# pcb.net
KiCad netlist of a schematic drawn in EAGLE
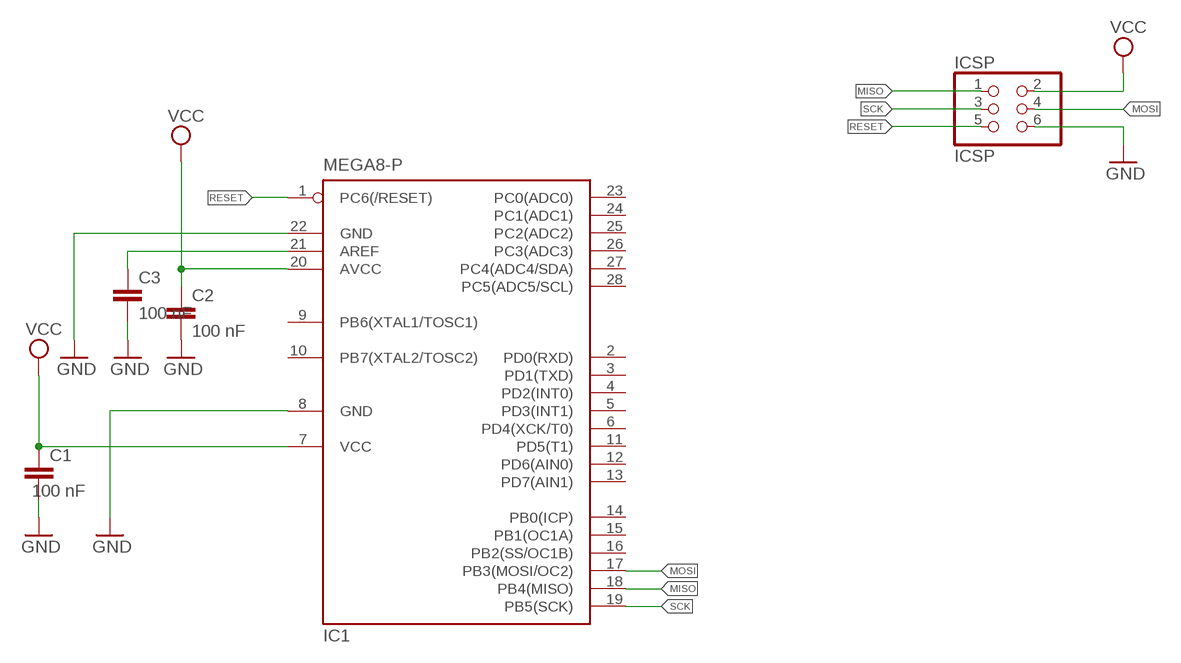
[diagram p0: schematic, sheet 1]

(export (version "E")
  (design (tool "Eeschema 10.0.6"))
  (components
    (comp (ref "C1")
      (value "100 nF")
      (footprint "eagle-import:C025-024X044")
      (libsource (lib "eagle-import") (part "C-EU025-024X044"))
    )
    (comp (ref "C2")
      (value "100 nF")
      (footprint "eagle-import:C025-024X044")
      (libsource (lib "eagle-import") (part "C-EU025-024X044"))
    )
    (comp (ref "C3")
      (value "100 nF")
      (footprint "eagle-import:C025-024X044")
      (libsource (lib "eagle-import") (part "C-EU025-024X044"))
    )
    (comp (ref "IC1")
      (value "MEGA8-P")
      (footprint "eagle-import:DIL28-3")
      (libsource (lib "eagle-import") (part "MEGA8-P"))
    )
    (comp (ref "ICSP")
      (value "ICSP")
      (footprint "eagle-import:2X03")
      (libsource (lib "eagle-import") (part "PINHD-2X3"))
    )
  )
  (nets
    (net (code "1") (name "GND") (class "Default")
      (node (ref "C1") (pin "2") (pinfunction "2_2") (pintype "passive"))
      (node (ref "C2") (pin "2") (pinfunction "2_2") (pintype "passive"))
      (node (ref "C3") (pin "2") (pinfunction "2_2") (pintype "passive"))
      (node (ref "IC1") (pin "22") (pinfunction "GND_22") (pintype "power_in"))
      (node (ref "IC1") (pin "8") (pinfunction "GND_8") (pintype "power_in"))
      (node (ref "ICSP") (pin "6") (pinfunction "6_6") (pintype "passive"))
    )
    (net (code "2") (name "MISO") (class "Default")
      (node (ref "IC1") (pin "18") (pinfunction "PB4(MISO)_18") (pintype "bidirectional"))
      (node (ref "ICSP") (pin "1") (pinfunction "1_1") (pintype "passive"))
    )
    (net (code "3") (name "MOSI") (class "Default")
      (node (ref "IC1") (pin "17") (pinfunction "PB3(MOSI/OC2)_17") (pintype "bidirectional"))
      (node (ref "ICSP") (pin "4") (pinfunction "4_4") (pintype "passive"))
    )
    (net (code "4") (name "Net-(IC1-AREF)") (class "Default")
      (node (ref "C3") (pin "1") (pinfunction "1_1") (pintype "passive"))
      (node (ref "IC1") (pin "21") (pinfunction "AREF_21") (pintype "passive"))
    )
    (net (code "5") (name "RESET") (class "Default")
      (node (ref "IC1") (pin "1") (pinfunction "PC6(/RESET)_1") (pintype "bidirectional"))
      (node (ref "ICSP") (pin "5") (pinfunction "5_5") (pintype "passive"))
    )
    (net (code "6") (name "SCK") (class "Default")
      (node (ref "IC1") (pin "19") (pinfunction "PB5(SCK)_19") (pintype "bidirectional"))
      (node (ref "ICSP") (pin "3") (pinfunction "3_3") (pintype "passive"))
    )
    (net (code "7") (name "VCC") (class "Default")
      (node (ref "C1") (pin "1") (pinfunction "1_1") (pintype "passive"))
      (node (ref "C2") (pin "1") (pinfunction "1_1") (pintype "passive"))
      (node (ref "IC1") (pin "20") (pinfunction "AVCC_20") (pintype "power_in"))
      (node (ref "IC1") (pin "7") (pinfunction "VCC_7") (pintype "power_in"))
      (node (ref "ICSP") (pin "2") (pinfunction "2_2") (pintype "passive"))
    )
    (net (code "8") (name "unconnected-(IC1-PB0(ICP)-Pad14)") (class "Default")
      (node (ref "IC1") (pin "14") (pinfunction "PB0(ICP)_14") (pintype "bidirectional"))
    )
    (net (code "9") (name "unconnected-(IC1-PB1(OC1A)-Pad15)") (class "Default")
      (node (ref "IC1") (pin "15") (pinfunction "PB1(OC1A)_15") (pintype "bidirectional"))
    )
    (net (code "10") (name "unconnected-(IC1-PB2(SS{slash}OC1B)-Pad16)") (class "Default")
      (node (ref "IC1") (pin "16") (pinfunction "PB2(SS/OC1B)_16") (pintype "bidirectional"))
    )
    (net (code "11") (name "unconnected-(IC1-PB6(XTAL1{slash}TOSC1)-Pad9)") (class "Default")
      (node (ref "IC1") (pin "9") (pinfunction "PB6(XTAL1/TOSC1)_9") (pintype "bidirectional"))
    )
    (net (code "12") (name "unconnected-(IC1-PB7(XTAL2{slash}TOSC2)-Pad10)") (class "Default")
      (node (ref "IC1") (pin "10") (pinfunction "PB7(XTAL2/TOSC2)_10") (pintype "bidirectional"))
    )
    (net (code "13") (name "unconnected-(IC1-PC0(ADC0)-Pad23)") (class "Default")
      (node (ref "IC1") (pin "23") (pinfunction "PC0(ADC0)_23") (pintype "bidirectional"))
    )
    (net (code "14") (name "unconnected-(IC1-PC1(ADC1)-Pad24)") (class "Default")
      (node (ref "IC1") (pin "24") (pinfunction "PC1(ADC1)_24") (pintype "bidirectional"))
    )
    (net (code "15") (name "unconnected-(IC1-PC2(ADC2)-Pad25)") (class "Default")
      (node (ref "IC1") (pin "25") (pinfunction "PC2(ADC2)_25") (pintype "bidirectional"))
    )
    (net (code "16") (name "unconnected-(IC1-PC3(ADC3)-Pad26)") (class "Default")
      (node (ref "IC1") (pin "26") (pinfunction "PC3(ADC3)_26") (pintype "bidirectional"))
    )
    (net (code "17") (name "unconnected-(IC1-PC4(ADC4{slash}SDA)-Pad27)") (class "Default")
      (node (ref "IC1") (pin "27") (pinfunction "PC4(ADC4/SDA)_27") (pintype "bidirectional"))
    )
    (net (code "18") (name "unconnected-(IC1-PC5(ADC5{slash}SCL)-Pad28)") (class "Default")
      (node (ref "IC1") (pin "28") (pinfunction "PC5(ADC5/SCL)_28") (pintype "bidirectional"))
    )
    (net (code "19") (name "unconnected-(IC1-PD0(RXD)-Pad2)") (class "Default")
      (node (ref "IC1") (pin "2") (pinfunction "PD0(RXD)_2") (pintype "bidirectional"))
    )
    (net (code "20") (name "unconnected-(IC1-PD1(TXD)-Pad3)") (class "Default")
      (node (ref "IC1") (pin "3") (pinfunction "PD1(TXD)_3") (pintype "bidirectional"))
    )
    (net (code "21") (name "unconnected-(IC1-PD2(INT0)-Pad4)") (class "Default")
      (node (ref "IC1") (pin "4") (pinfunction "PD2(INT0)_4") (pintype "bidirectional"))
    )
    (net (code "22") (name "unconnected-(IC1-PD3(INT1)-Pad5)") (class "Default")
      (node (ref "IC1") (pin "5") (pinfunction "PD3(INT1)_5") (pintype "bidirectional"))
    )
    (net (code "23") (name "unconnected-(IC1-PD4(XCK{slash}T0)-Pad6)") (class "Default")
      (node (ref "IC1") (pin "6") (pinfunction "PD4(XCK/T0)_6") (pintype "bidirectional"))
    )
    (net (code "24") (name "unconnected-(IC1-PD5(T1)-Pad11)") (class "Default")
      (node (ref "IC1") (pin "11") (pinfunction "PD5(T1)_11") (pintype "bidirectional"))
    )
    (net (code "25") (name "unconnected-(IC1-PD6(AIN0)-Pad12)") (class "Default")
      (node (ref "IC1") (pin "12") (pinfunction "PD6(AIN0)_12") (pintype "bidirectional"))
    )
    (net (code "26") (name "unconnected-(IC1-PD7(AIN1)-Pad13)") (class "Default")
      (node (ref "IC1") (pin "13") (pinfunction "PD7(AIN1)_13") (pintype "bidirectional"))
    )
  )
)
